# Power.net
KiCad netlist of a schematic drawn in Altium Designer
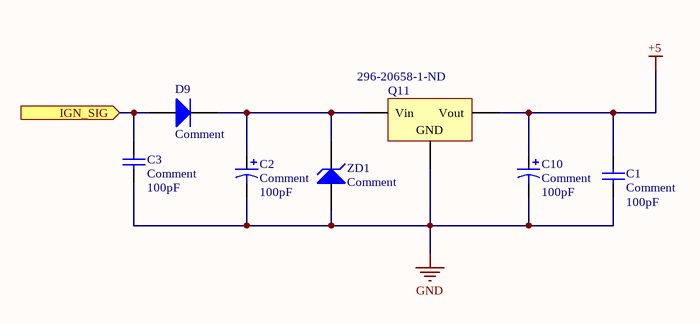
[diagram p0: Power.SchDoc]

(export (version "E")
  (design (tool "Eeschema 10.0.6"))
  (components
    (comp (ref "C1")
      (value "Comment")
      (footprint "J1-0603")
      (description "Capacitor (Semiconductor SIM Model)")
      (fields (field (name "ALTIUM_VALUE") "100pF") (field (name "PUBLISHER") "Altium Limited"))
      (libsource (lib "Miscellaneous Devices") (part "Cap Semi"))
    )
    (comp (ref "C2")
      (value "Comment")
      (footprint "6332[2512]")
      (description "Polarized Capacitor (Surface Mount)")
      (fields (field (name "ALTIUM_VALUE") "100pF") (field (name "PUBLISHER") "Altium Limited"))
      (libsource (lib "Miscellaneous Devices") (part "Cap Pol3"))
    )
    (comp (ref "C3")
      (value "Comment")
      (footprint "J1-0603")
      (description "Capacitor (Semiconductor SIM Model)")
      (fields (field (name "ALTIUM_VALUE") "100pF") (field (name "PUBLISHER") "Altium Limited"))
      (libsource (lib "") (part "Cap Semi_1"))
    )
    (comp (ref "C10")
      (value "Comment")
      (footprint "6332[2512]")
      (description "Polarized Capacitor (Surface Mount)")
      (fields (field (name "ALTIUM_VALUE") "100pF") (field (name "PUBLISHER") "Altium Limited"))
      (libsource (lib "Miscellaneous Devices") (part "Cap Pol3"))
    )
    (comp (ref "D9")
      (value "Comment")
      (footprint "SMC")
      (description "Default Diode")
      (fields (field (name "PUBLISHER") "Altium Limited"))
      (libsource (lib "Miscellaneous Devices") (part "Diode"))
    )
    (comp (ref "Q11")
      (value "~")
      (footprint "369A-13")
      (description "Voltage Regulator")
      (fields
        (field (name "SUPPLIER PART NUMBER 1") "296-20658-1-ND")
        (field (name "PUBLISHER") "Altium Limited")
      )
      (libsource (lib "Miscellaneous Devices") (part "Volt Reg"))
    )
    (comp (ref "ZD1")
      (value "Comment")
      (footprint "SMC")
      (description "Zener Diode")
      (fields (field (name "PUBLISHER") "Altium Limited"))
      (libsource (lib "Miscellaneous Devices") (part "D Zener"))
    )
  )
  (nets
    (net (code "1") (name "+5") (class "Default")
      (node (ref "C1") (pin "1") (pinfunction "1_1") (pintype "passive"))
      (node (ref "C10") (pin "1") (pinfunction "1_1") (pintype "passive"))
      (node (ref "Q11") (pin "3") (pinfunction "Vout_3") (pintype "passive"))
    )
    (net (code "2") (name "/IGN_SIG") (class "Default")
      (node (ref "C3") (pin "2") (pinfunction "2_2") (pintype "passive"))
      (node (ref "D9") (pin "1") (pinfunction "A_1") (pintype "passive"))
    )
    (net (code "3") (name "GND") (class "Default")
      (node (ref "C1") (pin "2") (pinfunction "2_2") (pintype "passive"))
      (node (ref "C10") (pin "2") (pinfunction "2_2") (pintype "passive"))
      (node (ref "C2") (pin "2") (pinfunction "2_2") (pintype "passive"))
      (node (ref "C3") (pin "1") (pinfunction "1_1") (pintype "passive"))
      (node (ref "Q11") (pin "2") (pinfunction "GND_2") (pintype "passive"))
      (node (ref "ZD1") (pin "1") (pinfunction "A_1") (pintype "passive"))
    )
    (net (code "4") (name "Net-(D9-K)") (class "Default")
      (node (ref "C2") (pin "1") (pinfunction "1_1") (pintype "passive"))
      (node (ref "D9") (pin "2") (pinfunction "K_2") (pintype "passive"))
      (node (ref "Q11") (pin "1") (pinfunction "Vin_1") (pintype "passive"))
      (node (ref "ZD1") (pin "2") (pinfunction "K_2") (pintype "passive"))
    )
  )
)
